# Sheet1.net
KiCad netlist of a schematic drawn in Altium Designer
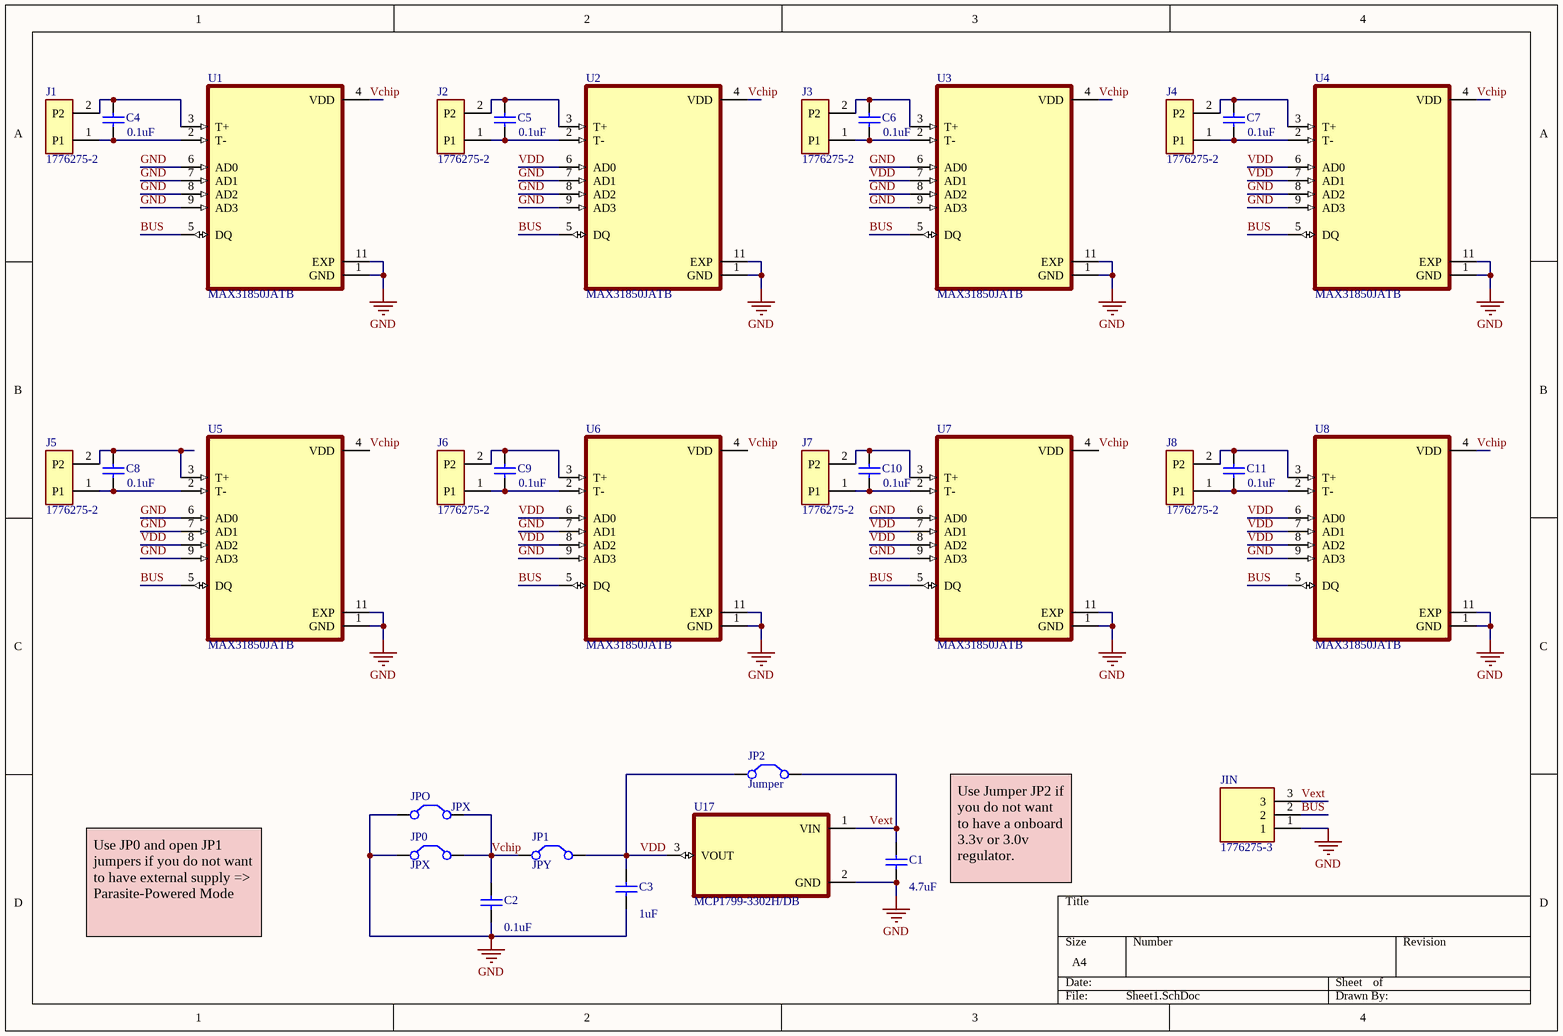
[diagram p0: Sheet1.SchDoc]

(export (version "E")
  (design (tool "Eeschema 10.0.6"))
  (components
    (comp (ref "C1")
      (value "4.7uF")
      (footprint "C0805")
      (description "Capacitor (Semiconductor SIM Model)")
      (fields (field (name "PUBLISHER") "Altium Limited"))
      (libsource (lib "Miscellaneous Devices") (part "Cap Semi"))
    )
    (comp (ref "C2")
      (value "0.1uF")
      (footprint "1608[0603]")
      (description "Capacitor (Semiconductor SIM Model)")
      (fields (field (name "PUBLISHER") "Altium Limited"))
      (libsource (lib "Miscellaneous Devices") (part "Cap Semi"))
    )
    (comp (ref "C3")
      (value "1uF")
      (footprint "1608[0603]")
      (description "Capacitor (Semiconductor SIM Model)")
      (fields (field (name "PUBLISHER") "Altium Limited"))
      (libsource (lib "Miscellaneous Devices") (part "Cap Semi"))
    )
    (comp (ref "C4")
      (value "0.1uF")
      (footprint "1608[0603]")
      (description "Capacitor (Semiconductor SIM Model)")
      (fields (field (name "PUBLISHER") "Altium Limited"))
      (libsource (lib "Miscellaneous Devices") (part "Cap Semi"))
    )
    (comp (ref "C5")
      (value "0.1uF")
      (footprint "1608[0603]")
      (description "Capacitor (Semiconductor SIM Model)")
      (fields (field (name "PUBLISHER") "Altium Limited"))
      (libsource (lib "Miscellaneous Devices") (part "Cap Semi"))
    )
    (comp (ref "C6")
      (value "0.1uF")
      (footprint "1608[0603]")
      (description "Capacitor (Semiconductor SIM Model)")
      (fields (field (name "PUBLISHER") "Altium Limited"))
      (libsource (lib "Miscellaneous Devices") (part "Cap Semi"))
    )
    (comp (ref "C7")
      (value "0.1uF")
      (footprint "1608[0603]")
      (description "Capacitor (Semiconductor SIM Model)")
      (fields (field (name "PUBLISHER") "Altium Limited"))
      (libsource (lib "Miscellaneous Devices") (part "Cap Semi"))
    )
    (comp (ref "C8")
      (value "0.1uF")
      (footprint "1608[0603]")
      (description "Capacitor (Semiconductor SIM Model)")
      (fields (field (name "PUBLISHER") "Altium Limited"))
      (libsource (lib "Miscellaneous Devices") (part "Cap Semi"))
    )
    (comp (ref "C9")
      (value "0.1uF")
      (footprint "1608[0603]")
      (description "Capacitor (Semiconductor SIM Model)")
      (fields (field (name "PUBLISHER") "Altium Limited"))
      (libsource (lib "Miscellaneous Devices") (part "Cap Semi"))
    )
    (comp (ref "C10")
      (value "0.1uF")
      (footprint "1608[0603]")
      (description "Capacitor (Semiconductor SIM Model)")
      (fields (field (name "PUBLISHER") "Altium Limited"))
      (libsource (lib "Miscellaneous Devices") (part "Cap Semi"))
    )
    (comp (ref "C11")
      (value "0.1uF")
      (footprint "1608[0603]")
      (description "Capacitor (Semiconductor SIM Model)")
      (fields (field (name "PUBLISHER") "Altium Limited"))
      (libsource (lib "Miscellaneous Devices") (part "Cap Semi"))
    )
    (comp (ref "J1")
      (value "1776275-2")
      (footprint "1776275-2:TE_1776275-2")
      (description "TERM BLOCK 2POS SIDE ENT 3.5MM")
      (fields (field (name "MF") "{'manufacturer': u'TE Connectivity'}"))
      (libsource (lib "*") (part "1776275-2"))
    )
    (comp (ref "J2")
      (value "1776275-2")
      (footprint "1776275-2:TE_1776275-2")
      (description "TERM BLOCK 2POS SIDE ENT 3.5MM")
      (fields (field (name "MF") "{'manufacturer': u'TE Connectivity'}"))
      (libsource (lib "*") (part "1776275-2"))
    )
    (comp (ref "J3")
      (value "1776275-2")
      (footprint "1776275-2:TE_1776275-2")
      (description "TERM BLOCK 2POS SIDE ENT 3.5MM")
      (fields (field (name "MF") "{'manufacturer': u'TE Connectivity'}"))
      (libsource (lib "*") (part "1776275-2"))
    )
    (comp (ref "J4")
      (value "1776275-2")
      (footprint "1776275-2:TE_1776275-2")
      (description "TERM BLOCK 2POS SIDE ENT 3.5MM")
      (fields (field (name "MF") "{'manufacturer': u'TE Connectivity'}"))
      (libsource (lib "*") (part "1776275-2"))
    )
    (comp (ref "J5")
      (value "1776275-2")
      (footprint "1776275-2:TE_1776275-2")
      (description "TERM BLOCK 2POS SIDE ENT 3.5MM")
      (fields (field (name "MF") "{'manufacturer': u'TE Connectivity'}"))
      (libsource (lib "*") (part "1776275-2"))
    )
    (comp (ref "J6")
      (value "1776275-2")
      (footprint "1776275-2:TE_1776275-2")
      (description "TERM BLOCK 2POS SIDE ENT 3.5MM")
      (fields (field (name "MF") "{'manufacturer': u'TE Connectivity'}"))
      (libsource (lib "*") (part "1776275-2"))
    )
    (comp (ref "J7")
      (value "1776275-2")
      (footprint "1776275-2:TE_1776275-2")
      (description "TERM BLOCK 2POS SIDE ENT 3.5MM")
      (fields (field (name "MF") "{'manufacturer': u'TE Connectivity'}"))
      (libsource (lib "*") (part "1776275-2"))
    )
    (comp (ref "J8")
      (value "1776275-2")
      (footprint "1776275-2:TE_1776275-2")
      (description "TERM BLOCK 2POS SIDE ENT 3.5MM")
      (fields (field (name "MF") "{'manufacturer': u'TE Connectivity'}"))
      (libsource (lib "*") (part "1776275-2"))
    )
    (comp (ref "JIN")
      (value "1776275-3")
      (footprint "1776275-3:TE_1776275-3")
      (fields (field (name "MF") "{'manufacturer': u'TE Connectivity'}"))
      (libsource (lib "*") (part "1776275-3"))
    )
    (comp (ref "JP0")
      (value "JPX")
      (footprint "1608[0603]")
      (description "Jumper Wire")
      (fields (field (name "PUBLISHER") "Altium Limited"))
      (libsource (lib "Miscellaneous Devices") (part "Jumper"))
    )
    (comp (ref "JP1")
      (value "JPY")
      (footprint "6-0805_L")
      (description "Jumper Wire")
      (fields (field (name "PUBLISHER") "Altium Limited"))
      (libsource (lib "Miscellaneous Devices") (part "Jumper"))
    )
    (comp (ref "JP2")
      (value "Jumper")
      (footprint "6-0805_L")
      (description "Jumper Wire")
      (fields (field (name "PUBLISHER") "Altium Limited"))
      (libsource (lib "Miscellaneous Devices") (part "Jumper"))
    )
    (comp (ref "JPO")
      (value "JPX")
      (footprint "1608[0603]")
      (description "Jumper Wire")
      (fields (field (name "PUBLISHER") "Altium Limited"))
      (libsource (lib "Miscellaneous Devices") (part "Jumper"))
    )
    (comp (ref "U1")
      (value "MAX31850JATB")
      (footprint "MAX31850JATB+:SON50P300X400X80-11N")
      (description "None")
      (fields (field (name "MF") "{'manufacturer': u'Maxim Integrated'}"))
      (libsource (lib "*") (part "MAX31850JATB"))
    )
    (comp (ref "U2")
      (value "MAX31850JATB")
      (footprint "MAX31850JATB+:SON50P300X400X80-11N")
      (description "None")
      (fields (field (name "MF") "{'manufacturer': u'Maxim Integrated'}"))
      (libsource (lib "*") (part "MAX31850JATB"))
    )
    (comp (ref "U3")
      (value "MAX31850JATB")
      (footprint "MAX31850JATB+:SON50P300X400X80-11N")
      (description "None")
      (fields (field (name "MF") "{'manufacturer': u'Maxim Integrated'}"))
      (libsource (lib "*") (part "MAX31850JATB"))
    )
    (comp (ref "U4")
      (value "MAX31850JATB")
      (footprint "MAX31850JATB+:SON50P300X400X80-11N")
      (description "None")
      (fields (field (name "MF") "{'manufacturer': u'Maxim Integrated'}"))
      (libsource (lib "*") (part "MAX31850JATB"))
    )
    (comp (ref "U5")
      (value "MAX31850JATB")
      (footprint "MAX31850JATB+:SON50P300X400X80-11N")
      (description "None")
      (fields (field (name "MF") "{'manufacturer': u'Maxim Integrated'}"))
      (libsource (lib "*") (part "MAX31850JATB"))
    )
    (comp (ref "U6")
      (value "MAX31850JATB")
      (footprint "MAX31850JATB+:SON50P300X400X80-11N")
      (description "None")
      (fields (field (name "MF") "{'manufacturer': u'Maxim Integrated'}"))
      (libsource (lib "*") (part "MAX31850JATB"))
    )
    (comp (ref "U7")
      (value "MAX31850JATB")
      (footprint "MAX31850JATB+:SON50P300X400X80-11N")
      (description "None")
      (fields (field (name "MF") "{'manufacturer': u'Maxim Integrated'}"))
      (libsource (lib "*") (part "MAX31850JATB"))
    )
    (comp (ref "U8")
      (value "MAX31850JATB")
      (footprint "MAX31850JATB+:SON50P300X400X80-11N")
      (description "None")
      (fields (field (name "MF") "{'manufacturer': u'Maxim Integrated'}"))
      (libsource (lib "*") (part "MAX31850JATB"))
    )
    (comp (ref "U17")
      (value "MCP1799-3302H/DB")
      (footprint "SOT230P700X180-4N")
      (fields (field (name "MP") "AP2114H-3.3TRG1") (field (name "MF") "{'manufacturer': u'Diodes Inc.'}"))
      (libsource (lib "AP2114H-3.3TRG1") (part "AP2114H-3.3TRG1"))
    )
  )
  (nets
    (net (code "1") (name "/BUS") (class "Default")
      (node (ref "JIN") (pin "2") (pinfunction "2_2") (pintype "passive"))
      (node (ref "U1") (pin "5") (pinfunction "DQ_5") (pintype "bidirectional"))
      (node (ref "U2") (pin "5") (pinfunction "DQ_5") (pintype "bidirectional"))
      (node (ref "U3") (pin "5") (pinfunction "DQ_5") (pintype "bidirectional"))
      (node (ref "U4") (pin "5") (pinfunction "DQ_5") (pintype "bidirectional"))
      (node (ref "U5") (pin "5") (pinfunction "DQ_5") (pintype "bidirectional"))
      (node (ref "U6") (pin "5") (pinfunction "DQ_5") (pintype "bidirectional"))
      (node (ref "U7") (pin "5") (pinfunction "DQ_5") (pintype "bidirectional"))
      (node (ref "U8") (pin "5") (pinfunction "DQ_5") (pintype "bidirectional"))
    )
    (net (code "2") (name "/VDD") (class "Default")
      (node (ref "C3") (pin "2") (pinfunction "2_2") (pintype "passive"))
      (node (ref "JP1") (pin "2") (pinfunction "C2_2") (pintype "passive"))
      (node (ref "JP2") (pin "1") (pinfunction "C1_1") (pintype "passive"))
      (node (ref "U17") (pin "3") (pinfunction "VOUT_3") (pintype "bidirectional"))
      (node (ref "U2") (pin "6") (pinfunction "AD0_6") (pintype "input"))
      (node (ref "U3") (pin "7") (pinfunction "AD1_7") (pintype "input"))
      (node (ref "U4") (pin "6") (pinfunction "AD0_6") (pintype "input"))
      (node (ref "U4") (pin "7") (pinfunction "AD1_7") (pintype "input"))
      (node (ref "U5") (pin "8") (pinfunction "AD2_8") (pintype "input"))
      (node (ref "U6") (pin "6") (pinfunction "AD0_6") (pintype "input"))
      (node (ref "U6") (pin "8") (pinfunction "AD2_8") (pintype "input"))
      (node (ref "U7") (pin "7") (pinfunction "AD1_7") (pintype "input"))
      (node (ref "U7") (pin "8") (pinfunction "AD2_8") (pintype "input"))
      (node (ref "U8") (pin "6") (pinfunction "AD0_6") (pintype "input"))
      (node (ref "U8") (pin "7") (pinfunction "AD1_7") (pintype "input"))
      (node (ref "U8") (pin "8") (pinfunction "AD2_8") (pintype "input"))
    )
    (net (code "3") (name "/Vchip") (class "Default")
      (node (ref "C2") (pin "2") (pinfunction "2_2") (pintype "passive"))
      (node (ref "JP0") (pin "2") (pinfunction "C2_2") (pintype "passive"))
      (node (ref "JP1") (pin "1") (pinfunction "C1_1") (pintype "passive"))
      (node (ref "JPO") (pin "2") (pinfunction "C2_2") (pintype "passive"))
      (node (ref "U1") (pin "4") (pinfunction "VDD_4") (pintype "power_in"))
      (node (ref "U2") (pin "4") (pinfunction "VDD_4") (pintype "power_in"))
      (node (ref "U3") (pin "4") (pinfunction "VDD_4") (pintype "power_in"))
      (node (ref "U4") (pin "4") (pinfunction "VDD_4") (pintype "power_in"))
      (node (ref "U5") (pin "4") (pinfunction "VDD_4") (pintype "power_in"))
      (node (ref "U6") (pin "4") (pinfunction "VDD_4") (pintype "power_in"))
      (node (ref "U7") (pin "4") (pinfunction "VDD_4") (pintype "power_in"))
      (node (ref "U8") (pin "4") (pinfunction "VDD_4") (pintype "power_in"))
    )
    (net (code "4") (name "/Vext") (class "Default")
      (node (ref "C1") (pin "2") (pinfunction "2_2") (pintype "passive"))
      (node (ref "JIN") (pin "3") (pinfunction "3_3") (pintype "passive"))
      (node (ref "JP2") (pin "2") (pinfunction "C2_2") (pintype "passive"))
      (node (ref "U17") (pin "1") (pinfunction "VIN_1") (pintype "power_in"))
    )
    (net (code "5") (name "GND") (class "Default")
      (node (ref "C1") (pin "1") (pinfunction "1_1") (pintype "passive"))
      (node (ref "C2") (pin "1") (pinfunction "1_1") (pintype "passive"))
      (node (ref "C3") (pin "1") (pinfunction "1_1") (pintype "passive"))
      (node (ref "JIN") (pin "1") (pinfunction "1_1") (pintype "passive"))
      (node (ref "JP0") (pin "1") (pinfunction "C1_1") (pintype "passive"))
      (node (ref "JPO") (pin "1") (pinfunction "C1_1") (pintype "passive"))
      (node (ref "U1") (pin "1") (pinfunction "GND_1") (pintype "power_in"))
      (node (ref "U1") (pin "11") (pinfunction "EXP_11") (pintype "power_in"))
      (node (ref "U1") (pin "6") (pinfunction "AD0_6") (pintype "input"))
      (node (ref "U1") (pin "7") (pinfunction "AD1_7") (pintype "input"))
      (node (ref "U1") (pin "8") (pinfunction "AD2_8") (pintype "input"))
      (node (ref "U1") (pin "9") (pinfunction "AD3_9") (pintype "input"))
      (node (ref "U17") (pin "2") (pinfunction "GND_2") (pintype "power_in"))
      (node (ref "U2") (pin "1") (pinfunction "GND_1") (pintype "power_in"))
      (node (ref "U2") (pin "11") (pinfunction "EXP_11") (pintype "power_in"))
      (node (ref "U2") (pin "7") (pinfunction "AD1_7") (pintype "input"))
      (node (ref "U2") (pin "8") (pinfunction "AD2_8") (pintype "input"))
      (node (ref "U2") (pin "9") (pinfunction "AD3_9") (pintype "input"))
      (node (ref "U3") (pin "1") (pinfunction "GND_1") (pintype "power_in"))
      (node (ref "U3") (pin "11") (pinfunction "EXP_11") (pintype "power_in"))
      (node (ref "U3") (pin "6") (pinfunction "AD0_6") (pintype "input"))
      (node (ref "U3") (pin "8") (pinfunction "AD2_8") (pintype "input"))
      (node (ref "U3") (pin "9") (pinfunction "AD3_9") (pintype "input"))
      (node (ref "U4") (pin "1") (pinfunction "GND_1") (pintype "power_in"))
      (node (ref "U4") (pin "11") (pinfunction "EXP_11") (pintype "power_in"))
      (node (ref "U4") (pin "8") (pinfunction "AD2_8") (pintype "input"))
      (node (ref "U4") (pin "9") (pinfunction "AD3_9") (pintype "input"))
      (node (ref "U5") (pin "1") (pinfunction "GND_1") (pintype "power_in"))
      (node (ref "U5") (pin "11") (pinfunction "EXP_11") (pintype "power_in"))
      (node (ref "U5") (pin "6") (pinfunction "AD0_6") (pintype "input"))
      (node (ref "U5") (pin "7") (pinfunction "AD1_7") (pintype "input"))
      (node (ref "U5") (pin "9") (pinfunction "AD3_9") (pintype "input"))
      (node (ref "U6") (pin "1") (pinfunction "GND_1") (pintype "power_in"))
      (node (ref "U6") (pin "11") (pinfunction "EXP_11") (pintype "power_in"))
      (node (ref "U6") (pin "7") (pinfunction "AD1_7") (pintype "input"))
      (node (ref "U6") (pin "9") (pinfunction "AD3_9") (pintype "input"))
      (node (ref "U7") (pin "1") (pinfunction "GND_1") (pintype "power_in"))
      (node (ref "U7") (pin "11") (pinfunction "EXP_11") (pintype "power_in"))
      (node (ref "U7") (pin "6") (pinfunction "AD0_6") (pintype "input"))
      (node (ref "U7") (pin "9") (pinfunction "AD3_9") (pintype "input"))
      (node (ref "U8") (pin "1") (pinfunction "GND_1") (pintype "power_in"))
      (node (ref "U8") (pin "11") (pinfunction "EXP_11") (pintype "power_in"))
      (node (ref "U8") (pin "9") (pinfunction "AD3_9") (pintype "input"))
    )
    (net (code "6") (name "Net-(J1-P1)") (class "Default")
      (node (ref "C4") (pin "1") (pinfunction "1_1") (pintype "passive"))
      (node (ref "J1") (pin "1") (pinfunction "P1_1") (pintype "passive"))
      (node (ref "U1") (pin "2") (pinfunction "T-_2") (pintype "input"))
    )
    (net (code "7") (name "Net-(J1-P2)") (class "Default")
      (node (ref "C4") (pin "2") (pinfunction "2_2") (pintype "passive"))
      (node (ref "J1") (pin "2") (pinfunction "P2_2") (pintype "passive"))
      (node (ref "U1") (pin "3") (pinfunction "T+_3") (pintype "input"))
    )
    (net (code "8") (name "Net-(J2-P1)") (class "Default")
      (node (ref "C5") (pin "1") (pinfunction "1_1") (pintype "passive"))
      (node (ref "J2") (pin "1") (pinfunction "P1_1") (pintype "passive"))
      (node (ref "U2") (pin "2") (pinfunction "T-_2") (pintype "input"))
    )
    (net (code "9") (name "Net-(J2-P2)") (class "Default")
      (node (ref "C5") (pin "2") (pinfunction "2_2") (pintype "passive"))
      (node (ref "J2") (pin "2") (pinfunction "P2_2") (pintype "passive"))
      (node (ref "U2") (pin "3") (pinfunction "T+_3") (pintype "input"))
    )
    (net (code "10") (name "Net-(J3-P1)") (class "Default")
      (node (ref "C6") (pin "1") (pinfunction "1_1") (pintype "passive"))
      (node (ref "J3") (pin "1") (pinfunction "P1_1") (pintype "passive"))
      (node (ref "U3") (pin "2") (pinfunction "T-_2") (pintype "input"))
    )
    (net (code "11") (name "Net-(J3-P2)") (class "Default")
      (node (ref "C6") (pin "2") (pinfunction "2_2") (pintype "passive"))
      (node (ref "J3") (pin "2") (pinfunction "P2_2") (pintype "passive"))
      (node (ref "U3") (pin "3") (pinfunction "T+_3") (pintype "input"))
    )
    (net (code "12") (name "Net-(J4-P1)") (class "Default")
      (node (ref "C7") (pin "1") (pinfunction "1_1") (pintype "passive"))
      (node (ref "J4") (pin "1") (pinfunction "P1_1") (pintype "passive"))
      (node (ref "U4") (pin "2") (pinfunction "T-_2") (pintype "input"))
    )
    (net (code "13") (name "Net-(J4-P2)") (class "Default")
      (node (ref "C7") (pin "2") (pinfunction "2_2") (pintype "passive"))
      (node (ref "J4") (pin "2") (pinfunction "P2_2") (pintype "passive"))
      (node (ref "U4") (pin "3") (pinfunction "T+_3") (pintype "input"))
    )
    (net (code "14") (name "Net-(J5-P1)") (class "Default")
      (node (ref "C8") (pin "1") (pinfunction "1_1") (pintype "passive"))
      (node (ref "J5") (pin "1") (pinfunction "P1_1") (pintype "passive"))
      (node (ref "U5") (pin "2") (pinfunction "T-_2") (pintype "input"))
    )
    (net (code "15") (name "Net-(J5-P2)") (class "Default")
      (node (ref "C8") (pin "2") (pinfunction "2_2") (pintype "passive"))
      (node (ref "J5") (pin "2") (pinfunction "P2_2") (pintype "passive"))
      (node (ref "U5") (pin "3") (pinfunction "T+_3") (pintype "input"))
    )
    (net (code "16") (name "Net-(J6-P1)") (class "Default")
      (node (ref "C9") (pin "1") (pinfunction "1_1") (pintype "passive"))
      (node (ref "J6") (pin "1") (pinfunction "P1_1") (pintype "passive"))
      (node (ref "U6") (pin "2") (pinfunction "T-_2") (pintype "input"))
    )
    (net (code "17") (name "Net-(J6-P2)") (class "Default")
      (node (ref "C9") (pin "2") (pinfunction "2_2") (pintype "passive"))
      (node (ref "J6") (pin "2") (pinfunction "P2_2") (pintype "passive"))
      (node (ref "U6") (pin "3") (pinfunction "T+_3") (pintype "input"))
    )
    (net (code "18") (name "Net-(J7-P1)") (class "Default")
      (node (ref "C10") (pin "1") (pinfunction "1_1") (pintype "passive"))
      (node (ref "J7") (pin "1") (pinfunction "P1_1") (pintype "passive"))
      (node (ref "U7") (pin "2") (pinfunction "T-_2") (pintype "input"))
    )
    (net (code "19") (name "Net-(J7-P2)") (class "Default")
      (node (ref "C10") (pin "2") (pinfunction "2_2") (pintype "passive"))
      (node (ref "J7") (pin "2") (pinfunction "P2_2") (pintype "passive"))
      (node (ref "U7") (pin "3") (pinfunction "T+_3") (pintype "input"))
    )
    (net (code "20") (name "Net-(J8-P1)") (class "Default")
      (node (ref "C11") (pin "1") (pinfunction "1_1") (pintype "passive"))
      (node (ref "J8") (pin "1") (pinfunction "P1_1") (pintype "passive"))
      (node (ref "U8") (pin "2") (pinfunction "T-_2") (pintype "input"))
    )
    (net (code "21") (name "Net-(J8-P2)") (class "Default")
      (node (ref "C11") (pin "2") (pinfunction "2_2") (pintype "passive"))
      (node (ref "J8") (pin "2") (pinfunction "P2_2") (pintype "passive"))
      (node (ref "U8") (pin "3") (pinfunction "T+_3") (pintype "input"))
    )
  )
)
